# design.net
KiCad netlist of a schematic drawn in EAGLE
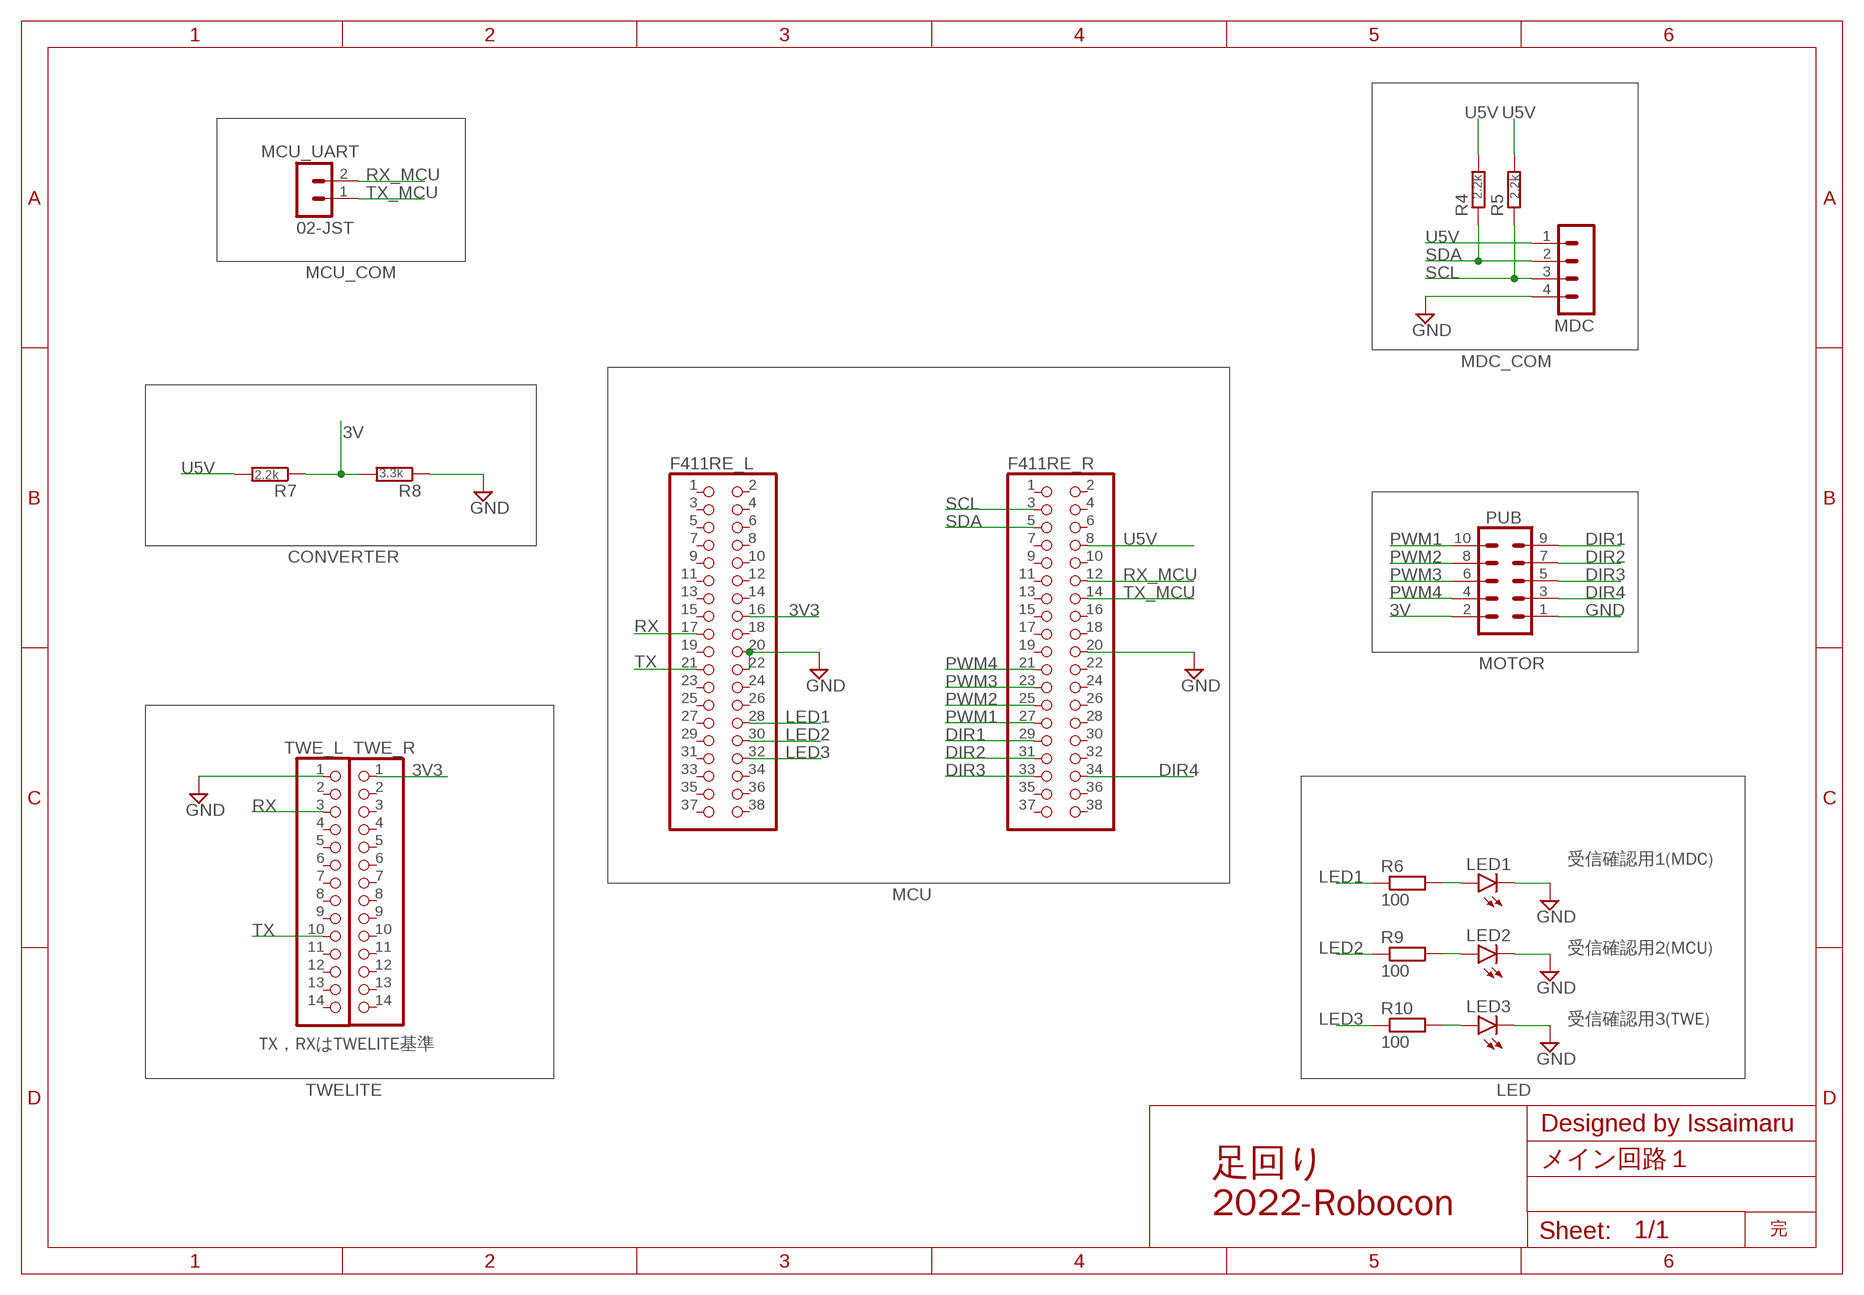
[diagram p0: schematic, sheet 1]

(export (version "E")
  (design (tool "Eeschema 10.0.6"))
  (components
    (comp (ref "F411RE_L")
      (value "PINHD-2X19")
      (footprint "eagle-import:2X19")
      (libsource (lib "eagle-import") (part "PINHD-2X19"))
    )
    (comp (ref "F411RE_R")
      (value "PINHD-2X19")
      (footprint "eagle-import:2X19")
      (libsource (lib "eagle-import") (part "PINHD-2X19"))
    )
    (comp (ref "LED1")
      (value "LED5MM")
      (footprint "eagle-import:LED5MM")
      (libsource (lib "eagle-import") (part "LED5MM"))
    )
    (comp (ref "LED2")
      (value "LED5MM")
      (footprint "eagle-import:LED5MM")
      (libsource (lib "eagle-import") (part "LED5MM"))
    )
    (comp (ref "LED3")
      (value "LED5MM")
      (footprint "eagle-import:LED5MM")
      (libsource (lib "eagle-import") (part "LED5MM"))
    )
    (comp (ref "MCU_UART")
      (value "02-JST")
      (footprint "eagle-import:B2B-XH")
      (libsource (lib "eagle-import") (part "02-JST"))
    )
    (comp (ref "MDC")
      (value "04-JST")
      (footprint "eagle-import:B4B-XH")
      (libsource (lib "eagle-import") (part "04-JST"))
    )
    (comp (ref "PUB")
      (value "ML10")
      (footprint "eagle-import:ML10")
      (libsource (lib "eagle-import") (part "ML10"))
    )
    (comp (ref "R4")
      (value "2.2k")
      (footprint "eagle-import:0204_7")
      (libsource (lib "eagle-import") (part "R-EU_0204/7"))
    )
    (comp (ref "R5")
      (value "2.2k")
      (footprint "eagle-import:0204_7")
      (libsource (lib "eagle-import") (part "R-EU_0204/7"))
    )
    (comp (ref "R6")
      (value "100")
      (footprint "eagle-import:0204_7")
      (libsource (lib "eagle-import") (part "R-EU_0204/7"))
    )
    (comp (ref "R7")
      (value "2.2k")
      (footprint "eagle-import:0204_7")
      (libsource (lib "eagle-import") (part "R-EU_0204/7"))
    )
    (comp (ref "R8")
      (value "3.3k")
      (footprint "eagle-import:0204_7")
      (libsource (lib "eagle-import") (part "R-EU_0204/7"))
    )
    (comp (ref "R9")
      (value "100")
      (footprint "eagle-import:0204_7")
      (libsource (lib "eagle-import") (part "R-EU_0204/7"))
    )
    (comp (ref "R10")
      (value "100")
      (footprint "eagle-import:0204_7")
      (libsource (lib "eagle-import") (part "R-EU_0204/7"))
    )
    (comp (ref "TWE_L")
      (value "PINHD-1X14")
      (footprint "eagle-import:1X14")
      (libsource (lib "eagle-import") (part "PINHD-1X14"))
    )
    (comp (ref "TWE_R")
      (value "PINHD-1X14")
      (footprint "eagle-import:1X14")
      (libsource (lib "eagle-import") (part "PINHD-1X14"))
    )
  )
  (nets
    (net (code "1") (name "/3V") (class "Default")
      (node (ref "PUB") (pin "2") (pinfunction "2_2") (pintype "passive"))
      (node (ref "R7") (pin "1") (pinfunction "1_1") (pintype "passive"))
      (node (ref "R8") (pin "2") (pinfunction "2_2") (pintype "passive"))
    )
    (net (code "2") (name "/3V3") (class "Default")
      (node (ref "F411RE_L") (pin "16") (pinfunction "16_16") (pintype "passive"))
      (node (ref "TWE_R") (pin "1") (pinfunction "1_1") (pintype "passive"))
    )
    (net (code "3") (name "/DIR1") (class "Default")
      (node (ref "F411RE_R") (pin "29") (pinfunction "29_29") (pintype "passive"))
      (node (ref "PUB") (pin "9") (pinfunction "9_9") (pintype "passive"))
    )
    (net (code "4") (name "/DIR2") (class "Default")
      (node (ref "F411RE_R") (pin "31") (pinfunction "31_31") (pintype "passive"))
      (node (ref "PUB") (pin "7") (pinfunction "7_7") (pintype "passive"))
    )
    (net (code "5") (name "/DIR3") (class "Default")
      (node (ref "F411RE_R") (pin "33") (pinfunction "33_33") (pintype "passive"))
      (node (ref "PUB") (pin "5") (pinfunction "5_5") (pintype "passive"))
    )
    (net (code "6") (name "/DIR4") (class "Default")
      (node (ref "F411RE_R") (pin "34") (pinfunction "34_34") (pintype "passive"))
      (node (ref "PUB") (pin "3") (pinfunction "3_3") (pintype "passive"))
    )
    (net (code "7") (name "/LED1") (class "Default")
      (node (ref "F411RE_L") (pin "28") (pinfunction "28_28") (pintype "passive"))
      (node (ref "R6") (pin "1") (pinfunction "1_1") (pintype "passive"))
    )
    (net (code "8") (name "/LED2") (class "Default")
      (node (ref "F411RE_L") (pin "30") (pinfunction "30_30") (pintype "passive"))
      (node (ref "R9") (pin "1") (pinfunction "1_1") (pintype "passive"))
    )
    (net (code "9") (name "/LED3") (class "Default")
      (node (ref "F411RE_L") (pin "32") (pinfunction "32_32") (pintype "passive"))
      (node (ref "R10") (pin "1") (pinfunction "1_1") (pintype "passive"))
    )
    (net (code "10") (name "/PWM1") (class "Default")
      (node (ref "F411RE_R") (pin "27") (pinfunction "27_27") (pintype "passive"))
      (node (ref "PUB") (pin "10") (pinfunction "10_10") (pintype "passive"))
    )
    (net (code "11") (name "/PWM2") (class "Default")
      (node (ref "F411RE_R") (pin "25") (pinfunction "25_25") (pintype "passive"))
      (node (ref "PUB") (pin "8") (pinfunction "8_8") (pintype "passive"))
    )
    (net (code "12") (name "/PWM3") (class "Default")
      (node (ref "F411RE_R") (pin "23") (pinfunction "23_23") (pintype "passive"))
      (node (ref "PUB") (pin "6") (pinfunction "6_6") (pintype "passive"))
    )
    (net (code "13") (name "/PWM4") (class "Default")
      (node (ref "F411RE_R") (pin "21") (pinfunction "21_21") (pintype "passive"))
      (node (ref "PUB") (pin "4") (pinfunction "4_4") (pintype "passive"))
    )
    (net (code "14") (name "/RX") (class "Default")
      (node (ref "F411RE_L") (pin "17") (pinfunction "17_17") (pintype "passive"))
      (node (ref "TWE_L") (pin "3") (pinfunction "3_3") (pintype "passive"))
    )
    (net (code "15") (name "/RX_MCU") (class "Default")
      (node (ref "F411RE_R") (pin "12") (pinfunction "12_12") (pintype "passive"))
      (node (ref "MCU_UART") (pin "2") (pinfunction "2_2") (pintype "passive"))
    )
    (net (code "16") (name "/SCL") (class "Default")
      (node (ref "F411RE_R") (pin "3") (pinfunction "3_3") (pintype "passive"))
      (node (ref "MDC") (pin "3") (pinfunction "3_3") (pintype "passive"))
      (node (ref "R5") (pin "1") (pinfunction "1_1") (pintype "passive"))
    )
    (net (code "17") (name "/SDA") (class "Default")
      (node (ref "F411RE_R") (pin "5") (pinfunction "5_5") (pintype "passive"))
      (node (ref "MDC") (pin "2") (pinfunction "2_2") (pintype "passive"))
      (node (ref "R4") (pin "1") (pinfunction "1_1") (pintype "passive"))
    )
    (net (code "18") (name "/TX") (class "Default")
      (node (ref "F411RE_L") (pin "21") (pinfunction "21_21") (pintype "passive"))
      (node (ref "TWE_L") (pin "10") (pinfunction "10_10") (pintype "passive"))
    )
    (net (code "19") (name "/TX_MCU") (class "Default")
      (node (ref "F411RE_R") (pin "14") (pinfunction "14_14") (pintype "passive"))
      (node (ref "MCU_UART") (pin "1") (pinfunction "1_1") (pintype "passive"))
    )
    (net (code "20") (name "/U5V") (class "Default")
      (node (ref "F411RE_R") (pin "8") (pinfunction "8_8") (pintype "passive"))
      (node (ref "MDC") (pin "1") (pinfunction "1_1") (pintype "passive"))
      (node (ref "R4") (pin "2") (pinfunction "2_2") (pintype "passive"))
      (node (ref "R5") (pin "2") (pinfunction "2_2") (pintype "passive"))
      (node (ref "R7") (pin "2") (pinfunction "2_2") (pintype "passive"))
    )
    (net (code "21") (name "GND") (class "Default")
      (node (ref "F411RE_L") (pin "20") (pinfunction "20_20") (pintype "passive"))
      (node (ref "F411RE_L") (pin "22") (pinfunction "22_22") (pintype "passive"))
      (node (ref "F411RE_R") (pin "20") (pinfunction "20_20") (pintype "passive"))
      (node (ref "LED1") (pin "K") (pinfunction "C_K") (pintype "passive"))
      (node (ref "LED2") (pin "K") (pinfunction "C_K") (pintype "passive"))
      (node (ref "LED3") (pin "K") (pinfunction "C_K") (pintype "passive"))
      (node (ref "MDC") (pin "4") (pinfunction "4_4") (pintype "passive"))
      (node (ref "PUB") (pin "1") (pinfunction "1_1") (pintype "passive"))
      (node (ref "R8") (pin "1") (pinfunction "1_1") (pintype "passive"))
      (node (ref "TWE_L") (pin "1") (pinfunction "1_1") (pintype "passive"))
    )
    (net (code "22") (name "Net-(LED1-PadA)") (class "Default")
      (node (ref "LED1") (pin "A") (pinfunction "A_A") (pintype "passive"))
      (node (ref "R6") (pin "2") (pinfunction "2_2") (pintype "passive"))
    )
    (net (code "23") (name "Net-(LED2-PadA)") (class "Default")
      (node (ref "LED2") (pin "A") (pinfunction "A_A") (pintype "passive"))
      (node (ref "R9") (pin "2") (pinfunction "2_2") (pintype "passive"))
    )
    (net (code "24") (name "Net-(LED3-PadA)") (class "Default")
      (node (ref "LED3") (pin "A") (pinfunction "A_A") (pintype "passive"))
      (node (ref "R10") (pin "2") (pinfunction "2_2") (pintype "passive"))
    )
    (net (code "25") (name "unconnected-(F411RE_L-Pad1)") (class "Default")
      (node (ref "F411RE_L") (pin "1") (pinfunction "1_1") (pintype "passive"))
    )
    (net (code "26") (name "unconnected-(F411RE_L-Pad2)") (class "Default")
      (node (ref "F411RE_L") (pin "2") (pinfunction "2_2") (pintype "passive"))
    )
    (net (code "27") (name "unconnected-(F411RE_L-Pad3)") (class "Default")
      (node (ref "F411RE_L") (pin "3") (pinfunction "3_3") (pintype "passive"))
    )
    (net (code "28") (name "unconnected-(F411RE_L-Pad4)") (class "Default")
      (node (ref "F411RE_L") (pin "4") (pinfunction "4_4") (pintype "passive"))
    )
    (net (code "29") (name "unconnected-(F411RE_L-Pad5)") (class "Default")
      (node (ref "F411RE_L") (pin "5") (pinfunction "5_5") (pintype "passive"))
    )
    (net (code "30") (name "unconnected-(F411RE_L-Pad6)") (class "Default")
      (node (ref "F411RE_L") (pin "6") (pinfunction "6_6") (pintype "passive"))
    )
    (net (code "31") (name "unconnected-(F411RE_L-Pad7)") (class "Default")
      (node (ref "F411RE_L") (pin "7") (pinfunction "7_7") (pintype "passive"))
    )
    (net (code "32") (name "unconnected-(F411RE_L-Pad8)") (class "Default")
      (node (ref "F411RE_L") (pin "8") (pinfunction "8_8") (pintype "passive"))
    )
    (net (code "33") (name "unconnected-(F411RE_L-Pad9)") (class "Default")
      (node (ref "F411RE_L") (pin "9") (pinfunction "9_9") (pintype "passive"))
    )
    (net (code "34") (name "unconnected-(F411RE_L-Pad10)") (class "Default")
      (node (ref "F411RE_L") (pin "10") (pinfunction "10_10") (pintype "passive"))
    )
    (net (code "35") (name "unconnected-(F411RE_L-Pad11)") (class "Default")
      (node (ref "F411RE_L") (pin "11") (pinfunction "11_11") (pintype "passive"))
    )
    (net (code "36") (name "unconnected-(F411RE_L-Pad12)") (class "Default")
      (node (ref "F411RE_L") (pin "12") (pinfunction "12_12") (pintype "passive"))
    )
    (net (code "37") (name "unconnected-(F411RE_L-Pad13)") (class "Default")
      (node (ref "F411RE_L") (pin "13") (pinfunction "13_13") (pintype "passive"))
    )
    (net (code "38") (name "unconnected-(F411RE_L-Pad14)") (class "Default")
      (node (ref "F411RE_L") (pin "14") (pinfunction "14_14") (pintype "passive"))
    )
    (net (code "39") (name "unconnected-(F411RE_L-Pad15)") (class "Default")
      (node (ref "F411RE_L") (pin "15") (pinfunction "15_15") (pintype "passive"))
    )
    (net (code "40") (name "unconnected-(F411RE_L-Pad18)") (class "Default")
      (node (ref "F411RE_L") (pin "18") (pinfunction "18_18") (pintype "passive"))
    )
    (net (code "41") (name "unconnected-(F411RE_L-Pad19)") (class "Default")
      (node (ref "F411RE_L") (pin "19") (pinfunction "19_19") (pintype "passive"))
    )
    (net (code "42") (name "unconnected-(F411RE_L-Pad23)") (class "Default")
      (node (ref "F411RE_L") (pin "23") (pinfunction "23_23") (pintype "passive"))
    )
    (net (code "43") (name "unconnected-(F411RE_L-Pad24)") (class "Default")
      (node (ref "F411RE_L") (pin "24") (pinfunction "24_24") (pintype "passive"))
    )
    (net (code "44") (name "unconnected-(F411RE_L-Pad25)") (class "Default")
      (node (ref "F411RE_L") (pin "25") (pinfunction "25_25") (pintype "passive"))
    )
    (net (code "45") (name "unconnected-(F411RE_L-Pad26)") (class "Default")
      (node (ref "F411RE_L") (pin "26") (pinfunction "26_26") (pintype "passive"))
    )
    (net (code "46") (name "unconnected-(F411RE_L-Pad27)") (class "Default")
      (node (ref "F411RE_L") (pin "27") (pinfunction "27_27") (pintype "passive"))
    )
    (net (code "47") (name "unconnected-(F411RE_L-Pad29)") (class "Default")
      (node (ref "F411RE_L") (pin "29") (pinfunction "29_29") (pintype "passive"))
    )
    (net (code "48") (name "unconnected-(F411RE_L-Pad31)") (class "Default")
      (node (ref "F411RE_L") (pin "31") (pinfunction "31_31") (pintype "passive"))
    )
    (net (code "49") (name "unconnected-(F411RE_L-Pad33)") (class "Default")
      (node (ref "F411RE_L") (pin "33") (pinfunction "33_33") (pintype "passive"))
    )
    (net (code "50") (name "unconnected-(F411RE_L-Pad34)") (class "Default")
      (node (ref "F411RE_L") (pin "34") (pinfunction "34_34") (pintype "passive"))
    )
    (net (code "51") (name "unconnected-(F411RE_L-Pad35)") (class "Default")
      (node (ref "F411RE_L") (pin "35") (pinfunction "35_35") (pintype "passive"))
    )
    (net (code "52") (name "unconnected-(F411RE_L-Pad36)") (class "Default")
      (node (ref "F411RE_L") (pin "36") (pinfunction "36_36") (pintype "passive"))
    )
    (net (code "53") (name "unconnected-(F411RE_L-Pad37)") (class "Default")
      (node (ref "F411RE_L") (pin "37") (pinfunction "37_37") (pintype "passive"))
    )
    (net (code "54") (name "unconnected-(F411RE_L-Pad38)") (class "Default")
      (node (ref "F411RE_L") (pin "38") (pinfunction "38_38") (pintype "passive"))
    )
    (net (code "55") (name "unconnected-(F411RE_R-Pad1)") (class "Default")
      (node (ref "F411RE_R") (pin "1") (pinfunction "1_1") (pintype "passive"))
    )
    (net (code "56") (name "unconnected-(F411RE_R-Pad2)") (class "Default")
      (node (ref "F411RE_R") (pin "2") (pinfunction "2_2") (pintype "passive"))
    )
    (net (code "57") (name "unconnected-(F411RE_R-Pad4)") (class "Default")
      (node (ref "F411RE_R") (pin "4") (pinfunction "4_4") (pintype "passive"))
    )
    (net (code "58") (name "unconnected-(F411RE_R-Pad6)") (class "Default")
      (node (ref "F411RE_R") (pin "6") (pinfunction "6_6") (pintype "passive"))
    )
    (net (code "59") (name "unconnected-(F411RE_R-Pad7)") (class "Default")
      (node (ref "F411RE_R") (pin "7") (pinfunction "7_7") (pintype "passive"))
    )
    (net (code "60") (name "unconnected-(F411RE_R-Pad9)") (class "Default")
      (node (ref "F411RE_R") (pin "9") (pinfunction "9_9") (pintype "passive"))
    )
    (net (code "61") (name "unconnected-(F411RE_R-Pad10)") (class "Default")
      (node (ref "F411RE_R") (pin "10") (pinfunction "10_10") (pintype "passive"))
    )
    (net (code "62") (name "unconnected-(F411RE_R-Pad11)") (class "Default")
      (node (ref "F411RE_R") (pin "11") (pinfunction "11_11") (pintype "passive"))
    )
    (net (code "63") (name "unconnected-(F411RE_R-Pad13)") (class "Default")
      (node (ref "F411RE_R") (pin "13") (pinfunction "13_13") (pintype "passive"))
    )
    (net (code "64") (name "unconnected-(F411RE_R-Pad15)") (class "Default")
      (node (ref "F411RE_R") (pin "15") (pinfunction "15_15") (pintype "passive"))
    )
    (net (code "65") (name "unconnected-(F411RE_R-Pad16)") (class "Default")
      (node (ref "F411RE_R") (pin "16") (pinfunction "16_16") (pintype "passive"))
    )
    (net (code "66") (name "unconnected-(F411RE_R-Pad17)") (class "Default")
      (node (ref "F411RE_R") (pin "17") (pinfunction "17_17") (pintype "passive"))
    )
    (net (code "67") (name "unconnected-(F411RE_R-Pad18)") (class "Default")
      (node (ref "F411RE_R") (pin "18") (pinfunction "18_18") (pintype "passive"))
    )
    (net (code "68") (name "unconnected-(F411RE_R-Pad19)") (class "Default")
      (node (ref "F411RE_R") (pin "19") (pinfunction "19_19") (pintype "passive"))
    )
    (net (code "69") (name "unconnected-(F411RE_R-Pad22)") (class "Default")
      (node (ref "F411RE_R") (pin "22") (pinfunction "22_22") (pintype "passive"))
    )
    (net (code "70") (name "unconnected-(F411RE_R-Pad24)") (class "Default")
      (node (ref "F411RE_R") (pin "24") (pinfunction "24_24") (pintype "passive"))
    )
    (net (code "71") (name "unconnected-(F411RE_R-Pad26)") (class "Default")
      (node (ref "F411RE_R") (pin "26") (pinfunction "26_26") (pintype "passive"))
    )
    (net (code "72") (name "unconnected-(F411RE_R-Pad28)") (class "Default")
      (node (ref "F411RE_R") (pin "28") (pinfunction "28_28") (pintype "passive"))
    )
    (net (code "73") (name "unconnected-(F411RE_R-Pad30)") (class "Default")
      (node (ref "F411RE_R") (pin "30") (pinfunction "30_30") (pintype "passive"))
    )
    (net (code "74") (name "unconnected-(F411RE_R-Pad32)") (class "Default")
      (node (ref "F411RE_R") (pin "32") (pinfunction "32_32") (pintype "passive"))
    )
    (net (code "75") (name "unconnected-(F411RE_R-Pad35)") (class "Default")
      (node (ref "F411RE_R") (pin "35") (pinfunction "35_35") (pintype "passive"))
    )
    (net (code "76") (name "unconnected-(F411RE_R-Pad36)") (class "Default")
      (node (ref "F411RE_R") (pin "36") (pinfunction "36_36") (pintype "passive"))
    )
    (net (code "77") (name "unconnected-(F411RE_R-Pad37)") (class "Default")
      (node (ref "F411RE_R") (pin "37") (pinfunction "37_37") (pintype "passive"))
    )
    (net (code "78") (name "unconnected-(F411RE_R-Pad38)") (class "Default")
      (node (ref "F411RE_R") (pin "38") (pinfunction "38_38") (pintype "passive"))
    )
    (net (code "79") (name "unconnected-(TWE_L-Pad2)") (class "Default")
      (node (ref "TWE_L") (pin "2") (pinfunction "2_2") (pintype "passive"))
    )
    (net (code "80") (name "unconnected-(TWE_L-Pad4)") (class "Default")
      (node (ref "TWE_L") (pin "4") (pinfunction "4_4") (pintype "passive"))
    )
    (net (code "81") (name "unconnected-(TWE_L-Pad5)") (class "Default")
      (node (ref "TWE_L") (pin "5") (pinfunction "5_5") (pintype "passive"))
    )
    (net (code "82") (name "unconnected-(TWE_L-Pad6)") (class "Default")
      (node (ref "TWE_L") (pin "6") (pinfunction "6_6") (pintype "passive"))
    )
    (net (code "83") (name "unconnected-(TWE_L-Pad7)") (class "Default")
      (node (ref "TWE_L") (pin "7") (pinfunction "7_7") (pintype "passive"))
    )
    (net (code "84") (name "unconnected-(TWE_L-Pad8)") (class "Default")
      (node (ref "TWE_L") (pin "8") (pinfunction "8_8") (pintype "passive"))
    )
    (net (code "85") (name "unconnected-(TWE_L-Pad9)") (class "Default")
      (node (ref "TWE_L") (pin "9") (pinfunction "9_9") (pintype "passive"))
    )
    (net (code "86") (name "unconnected-(TWE_L-Pad11)") (class "Default")
      (node (ref "TWE_L") (pin "11") (pinfunction "11_11") (pintype "passive"))
    )
    (net (code "87") (name "unconnected-(TWE_L-Pad12)") (class "Default")
      (node (ref "TWE_L") (pin "12") (pinfunction "12_12") (pintype "passive"))
    )
    (net (code "88") (name "unconnected-(TWE_L-Pad13)") (class "Default")
      (node (ref "TWE_L") (pin "13") (pinfunction "13_13") (pintype "passive"))
    )
    (net (code "89") (name "unconnected-(TWE_L-Pad14)") (class "Default")
      (node (ref "TWE_L") (pin "14") (pinfunction "14_14") (pintype "passive"))
    )
    (net (code "90") (name "unconnected-(TWE_R-Pad2)") (class "Default")
      (node (ref "TWE_R") (pin "2") (pinfunction "2_2") (pintype "passive"))
    )
    (net (code "91") (name "unconnected-(TWE_R-Pad3)") (class "Default")
      (node (ref "TWE_R") (pin "3") (pinfunction "3_3") (pintype "passive"))
    )
    (net (code "92") (name "unconnected-(TWE_R-Pad4)") (class "Default")
      (node (ref "TWE_R") (pin "4") (pinfunction "4_4") (pintype "passive"))
    )
    (net (code "93") (name "unconnected-(TWE_R-Pad5)") (class "Default")
      (node (ref "TWE_R") (pin "5") (pinfunction "5_5") (pintype "passive"))
    )
    (net (code "94") (name "unconnected-(TWE_R-Pad6)") (class "Default")
      (node (ref "TWE_R") (pin "6") (pinfunction "6_6") (pintype "passive"))
    )
    (net (code "95") (name "unconnected-(TWE_R-Pad7)") (class "Default")
      (node (ref "TWE_R") (pin "7") (pinfunction "7_7") (pintype "passive"))
    )
    (net (code "96") (name "unconnected-(TWE_R-Pad8)") (class "Default")
      (node (ref "TWE_R") (pin "8") (pinfunction "8_8") (pintype "passive"))
    )
    (net (code "97") (name "unconnected-(TWE_R-Pad9)") (class "Default")
      (node (ref "TWE_R") (pin "9") (pinfunction "9_9") (pintype "passive"))
    )
    (net (code "98") (name "unconnected-(TWE_R-Pad10)") (class "Default")
      (node (ref "TWE_R") (pin "10") (pinfunction "10_10") (pintype "passive"))
    )
    (net (code "99") (name "unconnected-(TWE_R-Pad11)") (class "Default")
      (node (ref "TWE_R") (pin "11") (pinfunction "11_11") (pintype "passive"))
    )
    (net (code "100") (name "unconnected-(TWE_R-Pad12)") (class "Default")
      (node (ref "TWE_R") (pin "12") (pinfunction "12_12") (pintype "passive"))
    )
    (net (code "101") (name "unconnected-(TWE_R-Pad13)") (class "Default")
      (node (ref "TWE_R") (pin "13") (pinfunction "13_13") (pintype "passive"))
    )
    (net (code "102") (name "unconnected-(TWE_R-Pad14)") (class "Default")
      (node (ref "TWE_R") (pin "14") (pinfunction "14_14") (pintype "passive"))
    )
  )
)
